# battery_weld.net
KiCad netlist of a schematic drawn in EAGLE
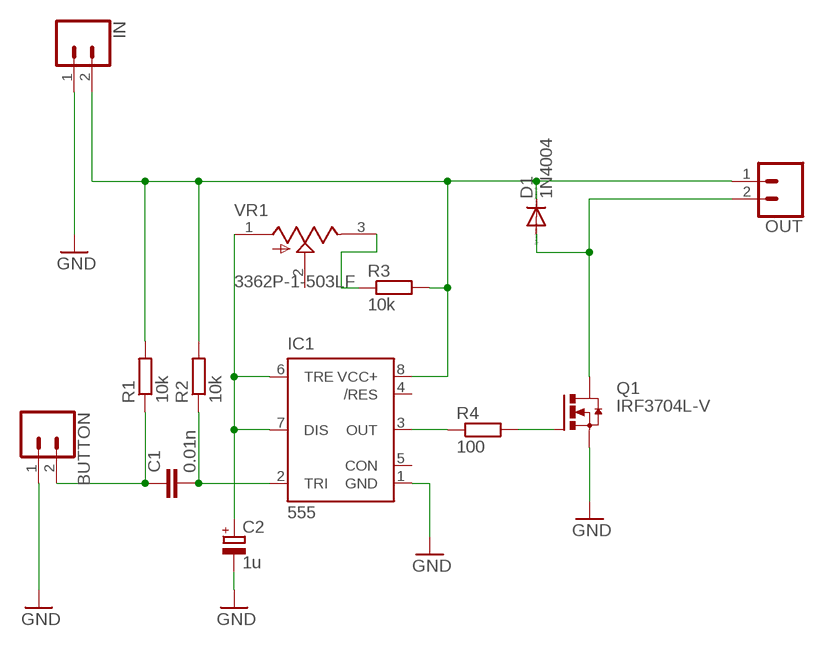
[diagram p0: schematic, sheet 1]

(export (version "E")
  (design (tool "Eeschema 10.0.6"))
  (components
    (comp (ref "BUTTON")
      (value "CONN_02")
      (footprint "eagle-import:1X02")
      (libsource (lib "eagle-import") (part "CONN_02"))
    )
    (comp (ref "C1")
      (value "0.01n")
      (footprint "eagle-import:C1206K")
      (libsource (lib "eagle-import") (part "C-EUC1206K"))
    )
    (comp (ref "C2")
      (value "1u")
      (footprint "eagle-import:E2-4")
      (libsource (lib "eagle-import") (part "CPOL-EUE2-4"))
    )
    (comp (ref "D1")
      (value "1N4004")
      (footprint "eagle-import:DO41-10")
      (libsource (lib "eagle-import") (part "1N4004"))
    )
    (comp (ref "IC1")
      (value "555")
      (footprint "eagle-import:SO08")
      (libsource (lib "eagle-import") (part "555D"))
    )
    (comp (ref "IN")
      (value "CONN_025MM")
      (footprint "eagle-import:SCREWTERMINAL-5MM-2")
      (libsource (lib "eagle-import") (part "CONN_025MM"))
    )
    (comp (ref "OUT")
      (value "CONN_025MM")
      (footprint "eagle-import:SCREWTERMINAL-5MM-2")
      (libsource (lib "eagle-import") (part "CONN_025MM"))
    )
    (comp (ref "Q1")
      (value "IRF3704L-V")
      (footprint "eagle-import:TO262-V")
      (libsource (lib "eagle-import") (part "IRF3704L-V"))
    )
    (comp (ref "R1")
      (value "10k")
      (footprint "eagle-import:M1206")
      (libsource (lib "eagle-import") (part "R-EU_M1206"))
    )
    (comp (ref "R2")
      (value "10k")
      (footprint "eagle-import:M1206")
      (libsource (lib "eagle-import") (part "R-EU_M1206"))
    )
    (comp (ref "R3")
      (value "10k")
      (footprint "eagle-import:M1206")
      (libsource (lib "eagle-import") (part "R-EU_M1206"))
    )
    (comp (ref "R4")
      (value "100")
      (footprint "eagle-import:M1206")
      (libsource (lib "eagle-import") (part "R-EU_M1206"))
    )
    (comp (ref "VR1")
      (value "3362P-1-503LF")
      (footprint "eagle-import:TRIM_3362P-1-503LF")
      (fields (field (name "MF") "Bourns"))
      (libsource (lib "eagle-import") (part "3362P-1-503LF"))
    )
  )
  (nets
    (net (code "1") (name "GND") (class "Default")
      (node (ref "BUTTON") (pin "1") (pinfunction "1_1") (pintype "passive"))
      (node (ref "C2") (pin "-") (pinfunction "-_-") (pintype "passive"))
      (node (ref "IC1") (pin "1") (pinfunction "GND_1") (pintype "power_in"))
      (node (ref "IN") (pin "1") (pinfunction "1_1") (pintype "passive"))
      (node (ref "Q1") (pin "3") (pinfunction "S_3") (pintype "passive"))
    )
    (net (code "2") (name "Net-(BUTTON-Pad2)") (class "Default")
      (node (ref "BUTTON") (pin "2") (pinfunction "2_2") (pintype "passive"))
      (node (ref "C1") (pin "1") (pinfunction "1_1") (pintype "passive"))
      (node (ref "R1") (pin "1") (pinfunction "1_1") (pintype "passive"))
    )
    (net (code "3") (name "Net-(IC1-DIS)") (class "Default")
      (node (ref "C2") (pin "+") (pinfunction "+_+") (pintype "passive"))
      (node (ref "IC1") (pin "6") (pinfunction "TRE_6") (pintype "input"))
      (node (ref "IC1") (pin "7") (pinfunction "DIS_7") (pintype "input"))
      (node (ref "VR1") (pin "1") (pinfunction "CCW_1") (pintype "passive"))
    )
    (net (code "4") (name "Net-(IC1-OUT)") (class "Default")
      (node (ref "IC1") (pin "3") (pinfunction "OUT_3") (pintype "output"))
      (node (ref "R4") (pin "1") (pinfunction "1_1") (pintype "passive"))
    )
    (net (code "5") (name "Net-(IC1-TRI)") (class "Default")
      (node (ref "C1") (pin "2") (pinfunction "2_2") (pintype "passive"))
      (node (ref "IC1") (pin "2") (pinfunction "TRI_2") (pintype "input"))
      (node (ref "R2") (pin "1") (pinfunction "1_1") (pintype "passive"))
    )
    (net (code "6") (name "Net-(IC1-VCC+)") (class "Default")
      (node (ref "D1") (pin "C") (pinfunction "C_C") (pintype "passive"))
      (node (ref "IC1") (pin "8") (pinfunction "VCC+_8") (pintype "power_in"))
      (node (ref "IN") (pin "2") (pinfunction "2_2") (pintype "passive"))
      (node (ref "OUT") (pin "1") (pinfunction "1_1") (pintype "passive"))
      (node (ref "R1") (pin "2") (pinfunction "2_2") (pintype "passive"))
      (node (ref "R2") (pin "2") (pinfunction "2_2") (pintype "passive"))
      (node (ref "R3") (pin "2") (pinfunction "2_2") (pintype "passive"))
    )
    (net (code "7") (name "Net-(Q1-D)") (class "Default")
      (node (ref "D1") (pin "A") (pinfunction "A_A") (pintype "passive"))
      (node (ref "OUT") (pin "2") (pinfunction "2_2") (pintype "passive"))
      (node (ref "Q1") (pin "2") (pinfunction "D_2") (pintype "passive"))
    )
    (net (code "8") (name "Net-(Q1-G)") (class "Default")
      (node (ref "Q1") (pin "1") (pinfunction "G_1") (pintype "passive"))
      (node (ref "R4") (pin "2") (pinfunction "2_2") (pintype "passive"))
    )
    (net (code "9") (name "Net-(VR1-CW)") (class "Default")
      (node (ref "R3") (pin "1") (pinfunction "1_1") (pintype "passive"))
      (node (ref "VR1") (pin "3") (pinfunction "CW_3") (pintype "passive"))
    )
    (net (code "10") (name "unconnected-(IC1-CON-Pad5)") (class "Default")
      (node (ref "IC1") (pin "5") (pinfunction "CON_5") (pintype "input"))
    )
    (net (code "11") (name "unconnected-(IC1-{slash}RES-Pad4)") (class "Default")
      (node (ref "IC1") (pin "4") (pinfunction "/RES_4") (pintype "input"))
    )
    (net (code "12") (name "unconnected-(VR1-WIPER-Pad2)") (class "Default")
      (node (ref "VR1") (pin "2") (pinfunction "WIPER_2") (pintype "passive"))
    )
  )
)
